# space_elevator.net
KiCad netlist of a schematic drawn in EAGLE
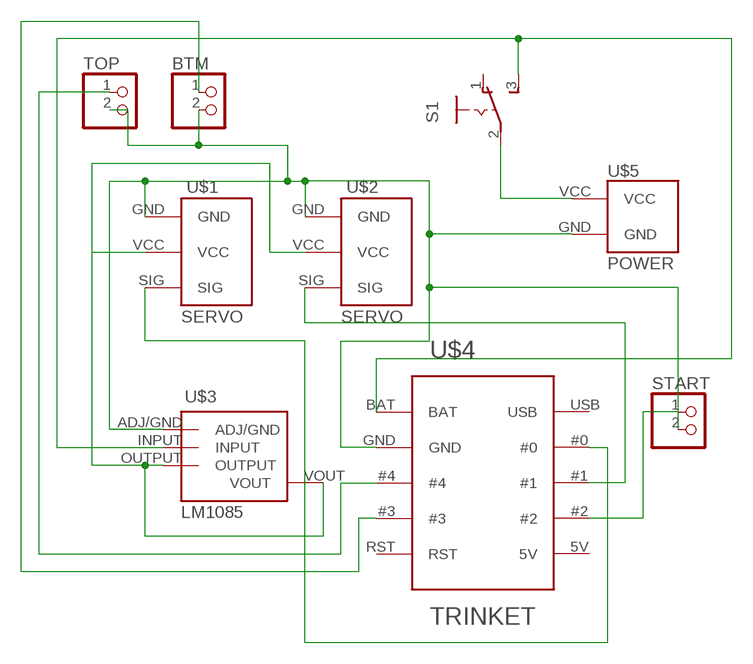
[diagram p0: schematic, sheet 1]

(export (version "E")
  (design (tool "Eeschema 10.0.6"))
  (components
    (comp (ref "BTM")
      (value "PINHD-1X2")
      (footprint "eagle-import:1X02")
      (libsource (lib "eagle-import") (part "PINHD-1X2"))
    )
    (comp (ref "S1")
      (value "255SB")
      (footprint "eagle-import:255SB")
      (libsource (lib "eagle-import") (part "255SB"))
    )
    (comp (ref "START")
      (value "PINHD-1X2")
      (footprint "eagle-import:1X02")
      (libsource (lib "eagle-import") (part "PINHD-1X2"))
    )
    (comp (ref "TOP")
      (value "PINHD-1X2")
      (footprint "eagle-import:1X02")
      (libsource (lib "eagle-import") (part "PINHD-1X2"))
    )
    (comp (ref "U$1")
      (value "SERVO")
      (footprint "eagle-import:SERVO")
      (libsource (lib "eagle-import") (part "SERVO"))
    )
    (comp (ref "U$2")
      (value "SERVO")
      (footprint "eagle-import:SERVO")
      (libsource (lib "eagle-import") (part "SERVO"))
    )
    (comp (ref "U$3")
      (value "LM1085")
      (footprint "eagle-import:TO220H")
      (libsource (lib "eagle-import") (part "LM1085"))
    )
    (comp (ref "U$4")
      (value "TRINKET")
      (footprint "eagle-import:TRINKETUSB")
      (libsource (lib "eagle-import") (part "TRINKET"))
    )
    (comp (ref "U$5")
      (value "POWER")
      (footprint "eagle-import:POWER")
      (libsource (lib "eagle-import") (part "POWER"))
    )
  )
  (nets
    (net (code "1") (name "Net-(BTM-Pad1)") (class "Default")
      (node (ref "BTM") (pin "1") (pinfunction "1_1") (pintype "passive"))
      (node (ref "U$4") (pin "#3") (pinfunction "#3_#3") (pintype "bidirectional"))
    )
    (net (code "2") (name "Net-(BTM-Pad2)") (class "Default")
      (node (ref "BTM") (pin "2") (pinfunction "2_2") (pintype "passive"))
      (node (ref "START") (pin "2") (pinfunction "2_2") (pintype "passive"))
      (node (ref "TOP") (pin "2") (pinfunction "2_2") (pintype "passive"))
      (node (ref "U$1") (pin "GND") (pinfunction "GND_GND") (pintype "bidirectional"))
      (node (ref "U$2") (pin "GND") (pinfunction "GND_GND") (pintype "bidirectional"))
      (node (ref "U$3") (pin "ADJ/GND") (pinfunction "ADJ/GND_ADJ/GND") (pintype "bidirectional"))
      (node (ref "U$4") (pin "GND") (pinfunction "GND_GND") (pintype "bidirectional"))
      (node (ref "U$5") (pin "GND") (pinfunction "GND_GND") (pintype "bidirectional"))
    )
    (net (code "3") (name "Net-(S1-P)") (class "Default")
      (node (ref "S1") (pin "2") (pinfunction "P_2") (pintype "passive"))
      (node (ref "U$5") (pin "VCC") (pinfunction "VCC_VCC") (pintype "bidirectional"))
    )
    (net (code "4") (name "Net-(S1-S)") (class "Default")
      (node (ref "S1") (pin "3") (pinfunction "S_3") (pintype "passive"))
      (node (ref "U$3") (pin "INPUT") (pinfunction "INPUT_INPUT") (pintype "bidirectional"))
      (node (ref "U$4") (pin "BAT") (pinfunction "BAT_BAT") (pintype "bidirectional"))
    )
    (net (code "5") (name "Net-(START-Pad1)") (class "Default")
      (node (ref "START") (pin "1") (pinfunction "1_1") (pintype "passive"))
      (node (ref "U$4") (pin "#2") (pinfunction "#2_#2") (pintype "bidirectional"))
    )
    (net (code "6") (name "Net-(TOP-Pad1)") (class "Default")
      (node (ref "TOP") (pin "1") (pinfunction "1_1") (pintype "passive"))
      (node (ref "U$4") (pin "#4") (pinfunction "#4_#4") (pintype "bidirectional"))
    )
    (net (code "7") (name "Net-(U$1-PadSIG)") (class "Default")
      (node (ref "U$1") (pin "SIG") (pinfunction "SIG_SIG") (pintype "bidirectional"))
      (node (ref "U$4") (pin "#0") (pinfunction "#0_#0") (pintype "bidirectional"))
    )
    (net (code "8") (name "Net-(U$1-PadVCC)") (class "Default")
      (node (ref "U$1") (pin "VCC") (pinfunction "VCC_VCC") (pintype "bidirectional"))
      (node (ref "U$2") (pin "VCC") (pinfunction "VCC_VCC") (pintype "bidirectional"))
      (node (ref "U$3") (pin "OUTPUT") (pinfunction "OUTPUT_OUTPUT") (pintype "bidirectional"))
      (node (ref "U$3") (pin "VOUT") (pinfunction "VOUT_VOUT") (pintype "bidirectional"))
    )
    (net (code "9") (name "Net-(U$2-PadSIG)") (class "Default")
      (node (ref "U$2") (pin "SIG") (pinfunction "SIG_SIG") (pintype "bidirectional"))
      (node (ref "U$4") (pin "#1") (pinfunction "#1_#1") (pintype "bidirectional"))
    )
    (net (code "10") (name "unconnected-(S1-O-Pad1)") (class "Default")
      (node (ref "S1") (pin "1") (pinfunction "O_1") (pintype "passive"))
    )
    (net (code "11") (name "unconnected-(U$4-Pad5V)") (class "Default")
      (node (ref "U$4") (pin "5V") (pinfunction "5V_5V") (pintype "bidirectional"))
    )
    (net (code "12") (name "unconnected-(U$4-PadRST)") (class "Default")
      (node (ref "U$4") (pin "RST") (pinfunction "RST_RST") (pintype "bidirectional"))
    )
    (net (code "13") (name "unconnected-(U$4-PadUSB)") (class "Default")
      (node (ref "U$4") (pin "USB") (pinfunction "USB_USB") (pintype "bidirectional"))
    )
  )
)
